# STM_WirelessModule.net
KiCad netlist of a schematic drawn in Altium Designer
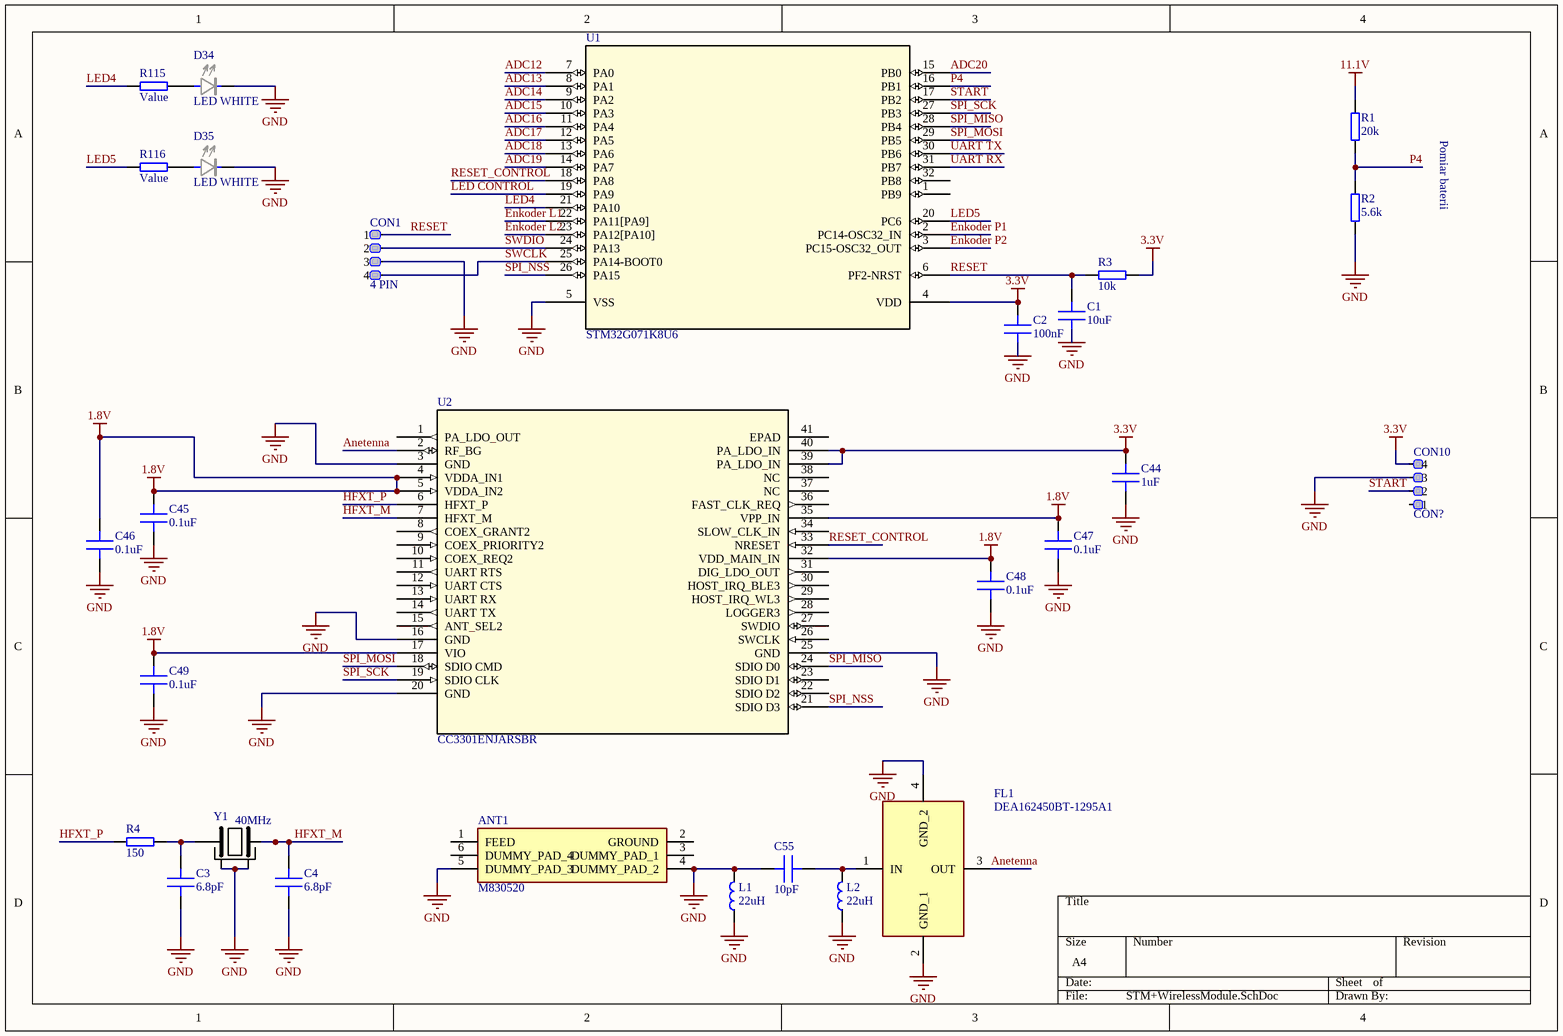
[diagram p0: STM+WirelessModule.SchDoc]

(export (version "E")
  (design (tool "Eeschema 10.0.6"))
  (components
    (comp (ref "ANT1")
      (value "M830520")
      (footprint "SamacSys:M830520")
      (description "Antenna")
      (fields (field (name "MOUSER PART NUMBER") "581-M830520"))
      (libsource (lib "*") (part "M830520"))
    )
    (comp (ref "C1")
      (value "10uF")
      (footprint "C 0603")
      (description "MLCC Capacitor")
      (libsource (lib "Components") (part "Capacitor"))
    )
    (comp (ref "C2")
      (value "100nF")
      (footprint "C 0603")
      (description "MLCC Capacitor")
      (libsource (lib "Components") (part "Capacitor"))
    )
    (comp (ref "C3")
      (value "6.8pF")
      (footprint "C 0603")
      (description "50V 6.8pF")
      (libsource (lib "Components") (part "Capacitor"))
    )
    (comp (ref "C4")
      (value "6.8pF")
      (footprint "C 0603")
      (description "50V 6.8pF")
      (libsource (lib "Components") (part "Capacitor"))
    )
    (comp (ref "C44")
      (value "1uF")
      (footprint "C 0603")
      (description "MLCC Capacitor")
      (libsource (lib "Components") (part "Capacitor"))
    )
    (comp (ref "C45")
      (value "0.1uF")
      (footprint "C 0603")
      (description "MLCC Capacitor")
      (libsource (lib "Components") (part "Capacitor"))
    )
    (comp (ref "C46")
      (value "0.1uF")
      (footprint "C 0603")
      (description "MLCC Capacitor")
      (libsource (lib "Components") (part "Capacitor"))
    )
    (comp (ref "C47")
      (value "0.1uF")
      (footprint "C 0603")
      (description "MLCC Capacitor")
      (libsource (lib "Components") (part "Capacitor"))
    )
    (comp (ref "C48")
      (value "0.1uF")
      (footprint "C 0603")
      (description "MLCC Capacitor")
      (libsource (lib "Components") (part "Capacitor"))
    )
    (comp (ref "C49")
      (value "0.1uF")
      (footprint "C 0603")
      (description "MLCC Capacitor")
      (libsource (lib "Components") (part "Capacitor"))
    )
    (comp (ref "C55")
      (value "10pF")
      (footprint "C 0603")
      (description "MLCC Capacitor")
      (libsource (lib "Components") (part "Capacitor"))
    )
    (comp (ref "CON1")
      (value "4 PIN")
      (footprint "BM04B-SRSS-TB")
      (libsource (lib "Connectors") (part "4 PIN"))
    )
    (comp (ref "CON10")
      (value "CON?")
      (footprint "Goldpin 1.27mm 4PIN")
      (libsource (lib "lib-all-components") (part "CON?"))
    )
    (comp (ref "D34")
      (value "LED WHITE")
      (footprint "LED 0603 White")
      (libsource (lib "Components2") (part "LED WHITE"))
    )
    (comp (ref "D35")
      (value "LED WHITE")
      (footprint "LED 0603 White")
      (libsource (lib "Components2") (part "LED WHITE"))
    )
    (comp (ref "FL1")
      (value "DEA162450BT-1295A1")
      (footprint "SamacSys:DEA162450BT1295A1")
      (description "Filter")
      (fields (field (name "MOUSER PART NUMBER") "810-DEA162450BT1295A"))
      (libsource (lib "*") (part "DEA162450BT-1295A1"))
    )
    (comp (ref "L1")
      (value "22uH")
      (footprint "L 1206")
      (description "General pourpouse inductor")
      (libsource (lib "Components2") (part "Inductor"))
    )
    (comp (ref "L2")
      (value "22uH")
      (footprint "L 1206")
      (description "General pourpouse inductor")
      (libsource (lib "Components2") (part "Inductor"))
    )
    (comp (ref "R1")
      (value "20k")
      (footprint "R 0603")
      (description "General pourpouse resistor")
      (libsource (lib "Components") (part "Resistor"))
    )
    (comp (ref "R2")
      (value "5.6k")
      (footprint "R 0603")
      (description "General pourpouse resistor")
      (libsource (lib "Components") (part "Resistor"))
    )
    (comp (ref "R3")
      (value "10k")
      (footprint "R 0603")
      (description "General pourpouse resistor")
      (libsource (lib "Components") (part "Resistor"))
    )
    (comp (ref "R4")
      (value "150")
      (footprint "R 0603")
      (description "General pourpouse resistor")
      (libsource (lib "Components") (part "Resistor"))
    )
    (comp (ref "R115")
      (value "Value")
      (footprint "R 0603")
      (description "General pourpouse resistor")
      (libsource (lib "Components") (part "Resistor"))
    )
    (comp (ref "R116")
      (value "Value")
      (footprint "R 0603")
      (description "General pourpouse resistor")
      (libsource (lib "Components") (part "Resistor"))
    )
    (comp (ref "U1")
      (value "STM32G071K8U6")
      (footprint "UFQFPN-32")
      (description "No Description Available")
      (fields (field (name "COPYRIGHT") "Copyright (C) 2024 Ultra Librarian. All rights reserved."))
      (libsource (lib "lib-all-components") (part "STM32G071K8U6"))
    )
    (comp (ref "U2")
      (value "CC3301ENJARSBR")
      (footprint "WQFN_JARSBR_TEX-M")
      (description "No Description Available")
      (libsource (lib "lib-all-components") (part "CC3301ENJARSBR"))
    )
    (comp (ref "Y1")
      (value "40MHz")
      (footprint "MCSJK7U1600123080B30")
      (description "Crystal or Oscillator")
      (fields (field (name "MANUFACTURER_PART_NUMBER") "MCSJK-7U-16.00-12-30-80-B-30"))
      (libsource (lib "lib-all-components") (part "MCSJK-7U-16.00-12-30-80-B-30"))
    )
  )
  (nets
    (net (code "1") (name "/ADC12") (class "Default")
      (node (ref "U1") (pin "7") (pinfunction "PA0_7") (pintype "bidirectional"))
    )
    (net (code "2") (name "/ADC13") (class "Default")
      (node (ref "U1") (pin "8") (pinfunction "PA1_8") (pintype "bidirectional"))
    )
    (net (code "3") (name "/ADC14") (class "Default")
      (node (ref "U1") (pin "9") (pinfunction "PA2_9") (pintype "bidirectional"))
    )
    (net (code "4") (name "/ADC15") (class "Default")
      (node (ref "U1") (pin "10") (pinfunction "PA3_10") (pintype "bidirectional"))
    )
    (net (code "5") (name "/ADC16") (class "Default")
      (node (ref "U1") (pin "11") (pinfunction "PA4_11") (pintype "bidirectional"))
    )
    (net (code "6") (name "/ADC17") (class "Default")
      (node (ref "U1") (pin "12") (pinfunction "PA5_12") (pintype "bidirectional"))
    )
    (net (code "7") (name "/ADC18") (class "Default")
      (node (ref "U1") (pin "13") (pinfunction "PA6_13") (pintype "bidirectional"))
    )
    (net (code "8") (name "/ADC19") (class "Default")
      (node (ref "U1") (pin "14") (pinfunction "PA7_14") (pintype "bidirectional"))
    )
    (net (code "9") (name "/ADC20") (class "Default")
      (node (ref "U1") (pin "15") (pinfunction "PB0_15") (pintype "bidirectional"))
    )
    (net (code "10") (name "/Anetenna") (class "Default")
      (node (ref "FL1") (pin "3") (pinfunction "OUT_3") (pintype "passive"))
      (node (ref "U2") (pin "2") (pinfunction "RF_BG_2") (pintype "bidirectional"))
    )
    (net (code "11") (name "/Enkoder L1") (class "Default")
      (node (ref "U1") (pin "22") (pinfunction "PA11[PA9]_22") (pintype "bidirectional"))
    )
    (net (code "12") (name "/Enkoder L2") (class "Default")
      (node (ref "U1") (pin "23") (pinfunction "PA12[PA10]_23") (pintype "bidirectional"))
    )
    (net (code "13") (name "/Enkoder P1") (class "Default")
      (node (ref "U1") (pin "2") (pinfunction "PC14-OSC32_IN_2") (pintype "bidirectional"))
    )
    (net (code "14") (name "/Enkoder P2") (class "Default")
      (node (ref "U1") (pin "3") (pinfunction "PC15-OSC32_OUT_3") (pintype "bidirectional"))
    )
    (net (code "15") (name "/HFXT_M") (class "Default")
      (node (ref "C4") (pin "2") (pinfunction "2_2") (pintype "passive"))
      (node (ref "U2") (pin "7") (pinfunction "HFXT_M_7") (pintype "passive"))
      (node (ref "Y1") (pin "3") (pinfunction "CRYSTAL_2_3") (pintype "passive"))
    )
    (net (code "16") (name "/HFXT_P") (class "Default")
      (node (ref "R4") (pin "2") (pinfunction "2_2") (pintype "passive"))
      (node (ref "U2") (pin "6") (pinfunction "HFXT_P_6") (pintype "passive"))
    )
    (net (code "17") (name "/LED CONTROL") (class "Default")
      (node (ref "U1") (pin "19") (pinfunction "PA9_19") (pintype "bidirectional"))
    )
    (net (code "18") (name "/LED4") (class "Default")
      (node (ref "R115") (pin "1") (pinfunction "1_1") (pintype "passive"))
      (node (ref "U1") (pin "21") (pinfunction "PA10_21") (pintype "bidirectional"))
    )
    (net (code "19") (name "/LED5") (class "Default")
      (node (ref "R116") (pin "1") (pinfunction "1_1") (pintype "passive"))
      (node (ref "U1") (pin "20") (pinfunction "PC6_20") (pintype "bidirectional"))
    )
    (net (code "20") (name "/P4") (class "Default")
      (node (ref "R1") (pin "1") (pinfunction "1_1") (pintype "passive"))
      (node (ref "R2") (pin "2") (pinfunction "2_2") (pintype "passive"))
      (node (ref "U1") (pin "16") (pinfunction "PB1_16") (pintype "bidirectional"))
    )
    (net (code "21") (name "/RESET") (class "Default")
      (node (ref "C1") (pin "2") (pinfunction "2_2") (pintype "passive"))
      (node (ref "CON1") (pin "1") (pinfunction "1_1") (pintype "passive"))
      (node (ref "R3") (pin "2") (pinfunction "2_2") (pintype "passive"))
      (node (ref "U1") (pin "6") (pinfunction "PF2-NRST_6") (pintype "bidirectional"))
    )
    (net (code "22") (name "/RESET_CONTROL") (class "Default")
      (node (ref "U1") (pin "18") (pinfunction "PA8_18") (pintype "bidirectional"))
      (node (ref "U2") (pin "33") (pinfunction "NRESET_33") (pintype "input"))
    )
    (net (code "23") (name "/SPI_MISO") (class "Default")
      (node (ref "U1") (pin "28") (pinfunction "PB4_28") (pintype "bidirectional"))
      (node (ref "U2") (pin "24") (pinfunction "SDIO_D0_24") (pintype "bidirectional"))
    )
    (net (code "24") (name "/SPI_MOSI") (class "Default")
      (node (ref "U1") (pin "29") (pinfunction "PB5_29") (pintype "bidirectional"))
      (node (ref "U2") (pin "18") (pinfunction "SDIO_CMD_18") (pintype "bidirectional"))
    )
    (net (code "25") (name "/SPI_NSS") (class "Default")
      (node (ref "U1") (pin "26") (pinfunction "PA15_26") (pintype "bidirectional"))
      (node (ref "U2") (pin "21") (pinfunction "SDIO_D3_21") (pintype "bidirectional"))
    )
    (net (code "26") (name "/SPI_SCK") (class "Default")
      (node (ref "U1") (pin "27") (pinfunction "PB3_27") (pintype "bidirectional"))
      (node (ref "U2") (pin "19") (pinfunction "SDIO_CLK_19") (pintype "input"))
    )
    (net (code "27") (name "/START") (class "Default")
      (node (ref "CON10") (pin "2") (pinfunction "2_2") (pintype "passive"))
      (node (ref "U1") (pin "17") (pinfunction "PB2_17") (pintype "bidirectional"))
    )
    (net (code "28") (name "/SWCLK") (class "Default")
      (node (ref "CON1") (pin "4") (pinfunction "4_4") (pintype "passive"))
      (node (ref "U1") (pin "25") (pinfunction "PA14-BOOT0_25") (pintype "bidirectional"))
    )
    (net (code "29") (name "/SWDIO") (class "Default")
      (node (ref "CON1") (pin "2") (pinfunction "2_2") (pintype "passive"))
      (node (ref "U1") (pin "24") (pinfunction "PA13_24") (pintype "bidirectional"))
    )
    (net (code "30") (name "/UART RX") (class "Default")
      (node (ref "U1") (pin "31") (pinfunction "PB7_31") (pintype "bidirectional"))
    )
    (net (code "31") (name "/UART TX") (class "Default")
      (node (ref "U1") (pin "30") (pinfunction "PB6_30") (pintype "bidirectional"))
    )
    (net (code "32") (name "1.8V") (class "Default")
      (node (ref "C45") (pin "2") (pinfunction "2_2") (pintype "passive"))
      (node (ref "C46") (pin "2") (pinfunction "2_2") (pintype "passive"))
      (node (ref "C47") (pin "2") (pinfunction "2_2") (pintype "passive"))
      (node (ref "C48") (pin "2") (pinfunction "2_2") (pintype "passive"))
      (node (ref "C49") (pin "2") (pinfunction "2_2") (pintype "passive"))
      (node (ref "U2") (pin "17") (pinfunction "VIO_17") (pintype "power_in"))
      (node (ref "U2") (pin "32") (pinfunction "VDD_MAIN_IN_32") (pintype "power_in"))
      (node (ref "U2") (pin "35") (pinfunction "VPP_IN_35") (pintype "power_in"))
      (node (ref "U2") (pin "4") (pinfunction "VDDA_IN1_4") (pintype "input"))
      (node (ref "U2") (pin "5") (pinfunction "VDDA_IN2_5") (pintype "input"))
    )
    (net (code "33") (name "3.3V") (class "Default")
      (node (ref "C2") (pin "2") (pinfunction "2_2") (pintype "passive"))
      (node (ref "C44") (pin "2") (pinfunction "2_2") (pintype "passive"))
      (node (ref "CON10") (pin "4") (pinfunction "4_4") (pintype "passive"))
      (node (ref "R3") (pin "1") (pinfunction "1_1") (pintype "passive"))
      (node (ref "U1") (pin "4") (pinfunction "VDD_4") (pintype "power_in"))
      (node (ref "U2") (pin "39") (pinfunction "PA_LDO_IN_39") (pintype "power_in"))
      (node (ref "U2") (pin "40") (pinfunction "PA_LDO_IN_40") (pintype "power_in"))
    )
    (net (code "34") (name "11.1V") (class "Default")
      (node (ref "R1") (pin "2") (pinfunction "2_2") (pintype "passive"))
    )
    (net (code "35") (name "GND") (class "Default")
      (node (ref "ANT1") (pin "4") (pinfunction "DUMMY_PAD_2_4") (pintype "passive"))
      (node (ref "ANT1") (pin "5") (pinfunction "DUMMY_PAD_3_5") (pintype "passive"))
      (node (ref "C1") (pin "1") (pinfunction "1_1") (pintype "passive"))
      (node (ref "C2") (pin "1") (pinfunction "1_1") (pintype "passive"))
      (node (ref "C3") (pin "1") (pinfunction "1_1") (pintype "passive"))
      (node (ref "C4") (pin "1") (pinfunction "1_1") (pintype "passive"))
      (node (ref "C44") (pin "1") (pinfunction "1_1") (pintype "passive"))
      (node (ref "C45") (pin "1") (pinfunction "1_1") (pintype "passive"))
      (node (ref "C46") (pin "1") (pinfunction "1_1") (pintype "passive"))
      (node (ref "C47") (pin "1") (pinfunction "1_1") (pintype "passive"))
      (node (ref "C48") (pin "1") (pinfunction "1_1") (pintype "passive"))
      (node (ref "C49") (pin "1") (pinfunction "1_1") (pintype "passive"))
      (node (ref "C55") (pin "2") (pinfunction "2_2") (pintype "passive"))
      (node (ref "CON1") (pin "3") (pinfunction "3_3") (pintype "passive"))
      (node (ref "CON10") (pin "3") (pinfunction "3_3") (pintype "passive"))
      (node (ref "D34") (pin "2") (pinfunction "2_2") (pintype "passive"))
      (node (ref "D35") (pin "2") (pinfunction "2_2") (pintype "passive"))
      (node (ref "FL1") (pin "2") (pinfunction "GND_1_2") (pintype "passive"))
      (node (ref "FL1") (pin "4") (pinfunction "GND_2_4") (pintype "passive"))
      (node (ref "L1") (pin "1") (pinfunction "1_1") (pintype "passive"))
      (node (ref "L1") (pin "2") (pinfunction "2_2") (pintype "passive"))
      (node (ref "L2") (pin "1") (pinfunction "1_1") (pintype "passive"))
      (node (ref "R2") (pin "1") (pinfunction "1_1") (pintype "passive"))
      (node (ref "U1") (pin "5") (pinfunction "VSS_5") (pintype "power_in"))
      (node (ref "U2") (pin "16") (pinfunction "GND_16") (pintype "power_in"))
      (node (ref "U2") (pin "20") (pinfunction "GND_20") (pintype "power_in"))
      (node (ref "U2") (pin "25") (pinfunction "GND_25") (pintype "power_in"))
      (node (ref "U2") (pin "3") (pinfunction "GND_3") (pintype "power_in"))
      (node (ref "Y1") (pin "2") (pinfunction "GND_1_2") (pintype "passive"))
      (node (ref "Y1") (pin "4") (pinfunction "GND_2_4") (pintype "passive"))
    )
    (net (code "36") (name "Net-(D34-Pad1)") (class "Default")
      (node (ref "D34") (pin "1") (pinfunction "1_1") (pintype "passive"))
      (node (ref "R115") (pin "2") (pinfunction "2_2") (pintype "passive"))
    )
    (net (code "37") (name "Net-(D35-Pad1)") (class "Default")
      (node (ref "D35") (pin "1") (pinfunction "1_1") (pintype "passive"))
      (node (ref "R116") (pin "2") (pinfunction "2_2") (pintype "passive"))
    )
    (net (code "38") (name "Net-(FL1-IN)") (class "Default")
      (node (ref "C55") (pin "1") (pinfunction "1_1") (pintype "passive"))
      (node (ref "FL1") (pin "1") (pinfunction "IN_1") (pintype "passive"))
      (node (ref "L2") (pin "2") (pinfunction "2_2") (pintype "passive"))
    )
    (net (code "39") (name "Net-(Y1-CRYSTAL_1)") (class "Default")
      (node (ref "C3") (pin "2") (pinfunction "2_2") (pintype "passive"))
      (node (ref "R4") (pin "1") (pinfunction "1_1") (pintype "passive"))
      (node (ref "Y1") (pin "1") (pinfunction "CRYSTAL_1_1") (pintype "passive"))
    )
    (net (code "40") (name "unconnected-(ANT1-DUMMY_PAD_1-Pad3)") (class "Default")
      (node (ref "ANT1") (pin "3") (pinfunction "DUMMY_PAD_1_3") (pintype "passive"))
    )
    (net (code "41") (name "unconnected-(ANT1-DUMMY_PAD_4-Pad6)") (class "Default")
      (node (ref "ANT1") (pin "6") (pinfunction "DUMMY_PAD_4_6") (pintype "passive"))
    )
    (net (code "42") (name "unconnected-(ANT1-FEED-Pad1)") (class "Default")
      (node (ref "ANT1") (pin "1") (pinfunction "FEED_1") (pintype "passive"))
    )
    (net (code "43") (name "unconnected-(ANT1-GROUND-Pad2)") (class "Default")
      (node (ref "ANT1") (pin "2") (pinfunction "GROUND_2") (pintype "passive"))
    )
    (net (code "44") (name "unconnected-(CON10-Pad1)") (class "Default")
      (node (ref "CON10") (pin "1") (pinfunction "1_1") (pintype "passive"))
    )
    (net (code "45") (name "unconnected-(U1-PB8-Pad32)") (class "Default")
      (node (ref "U1") (pin "32") (pinfunction "PB8_32") (pintype "bidirectional"))
    )
    (net (code "46") (name "unconnected-(U1-PB9-Pad1)") (class "Default")
      (node (ref "U1") (pin "1") (pinfunction "PB9_1") (pintype "bidirectional"))
    )
    (net (code "47") (name "unconnected-(U2-ANT_SEL2-Pad15)") (class "Default")
      (node (ref "U2") (pin "15") (pinfunction "ANT_SEL2_15") (pintype "output"))
    )
    (net (code "48") (name "unconnected-(U2-COEX_GRANT2-Pad8)") (class "Default")
      (node (ref "U2") (pin "8") (pinfunction "COEX_GRANT2_8") (pintype "output"))
    )
    (net (code "49") (name "unconnected-(U2-COEX_PRIORITY2-Pad9)") (class "Default")
      (node (ref "U2") (pin "9") (pinfunction "COEX_PRIORITY2_9") (pintype "input"))
    )
    (net (code "50") (name "unconnected-(U2-COEX_REQ2-Pad10)") (class "Default")
      (node (ref "U2") (pin "10") (pinfunction "COEX_REQ2_10") (pintype "input"))
    )
    (net (code "51") (name "unconnected-(U2-DIG_LDO_OUT-Pad31)") (class "Default")
      (node (ref "U2") (pin "31") (pinfunction "DIG_LDO_OUT_31") (pintype "output"))
    )
    (net (code "52") (name "unconnected-(U2-EPAD-Pad41)") (class "Default")
      (node (ref "U2") (pin "41") (pinfunction "EPAD_41") (pintype "power_in"))
    )
    (net (code "53") (name "unconnected-(U2-FAST_CLK_REQ-Pad36)") (class "Default")
      (node (ref "U2") (pin "36") (pinfunction "FAST_CLK_REQ_36") (pintype "output"))
    )
    (net (code "54") (name "unconnected-(U2-HOST_IRQ_BLE3-Pad30)") (class "Default")
      (node (ref "U2") (pin "30") (pinfunction "HOST_IRQ_BLE3_30") (pintype "output"))
    )
    (net (code "55") (name "unconnected-(U2-HOST_IRQ_WL3-Pad29)") (class "Default")
      (node (ref "U2") (pin "29") (pinfunction "HOST_IRQ_WL3_29") (pintype "output"))
    )
    (net (code "56") (name "unconnected-(U2-LOGGER3-Pad28)") (class "Default")
      (node (ref "U2") (pin "28") (pinfunction "LOGGER3_28") (pintype "output"))
    )
    (net (code "57") (name "unconnected-(U2-NC-Pad37)") (class "Default")
      (node (ref "U2") (pin "37") (pinfunction "NC_37") (pintype "passive"))
    )
    (net (code "58") (name "unconnected-(U2-NC-Pad38)") (class "Default")
      (node (ref "U2") (pin "38") (pinfunction "NC_38") (pintype "passive"))
    )
    (net (code "59") (name "unconnected-(U2-PA_LDO_OUT-Pad1)") (class "Default")
      (node (ref "U2") (pin "1") (pinfunction "PA_LDO_OUT_1") (pintype "output"))
    )
    (net (code "60") (name "unconnected-(U2-SDIO_D1-Pad23)") (class "Default")
      (node (ref "U2") (pin "23") (pinfunction "SDIO_D1_23") (pintype "bidirectional"))
    )
    (net (code "61") (name "unconnected-(U2-SDIO_D2-Pad22)") (class "Default")
      (node (ref "U2") (pin "22") (pinfunction "SDIO_D2_22") (pintype "bidirectional"))
    )
    (net (code "62") (name "unconnected-(U2-SLOW_CLK_IN-Pad34)") (class "Default")
      (node (ref "U2") (pin "34") (pinfunction "SLOW_CLK_IN_34") (pintype "input"))
    )
    (net (code "63") (name "unconnected-(U2-SWCLK-Pad26)") (class "Default")
      (node (ref "U2") (pin "26") (pinfunction "SWCLK_26") (pintype "input"))
    )
    (net (code "64") (name "unconnected-(U2-SWDIO-Pad27)") (class "Default")
      (node (ref "U2") (pin "27") (pinfunction "SWDIO_27") (pintype "bidirectional"))
    )
    (net (code "65") (name "unconnected-(U2-UART_CTS-Pad12)") (class "Default")
      (node (ref "U2") (pin "12") (pinfunction "UART_CTS_12") (pintype "input"))
    )
    (net (code "66") (name "unconnected-(U2-UART_RTS-Pad11)") (class "Default")
      (node (ref "U2") (pin "11") (pinfunction "UART_RTS_11") (pintype "output"))
    )
    (net (code "67") (name "unconnected-(U2-UART_RX-Pad13)") (class "Default")
      (node (ref "U2") (pin "13") (pinfunction "UART_RX_13") (pintype "input"))
    )
    (net (code "68") (name "unconnected-(U2-UART_TX-Pad14)") (class "Default")
      (node (ref "U2") (pin "14") (pinfunction "UART_TX_14") (pintype "output"))
    )
  )
)
